# SCH_usb_hub_2025-07-05.net
KiCad netlist of a schematic drawn in EasyEDA
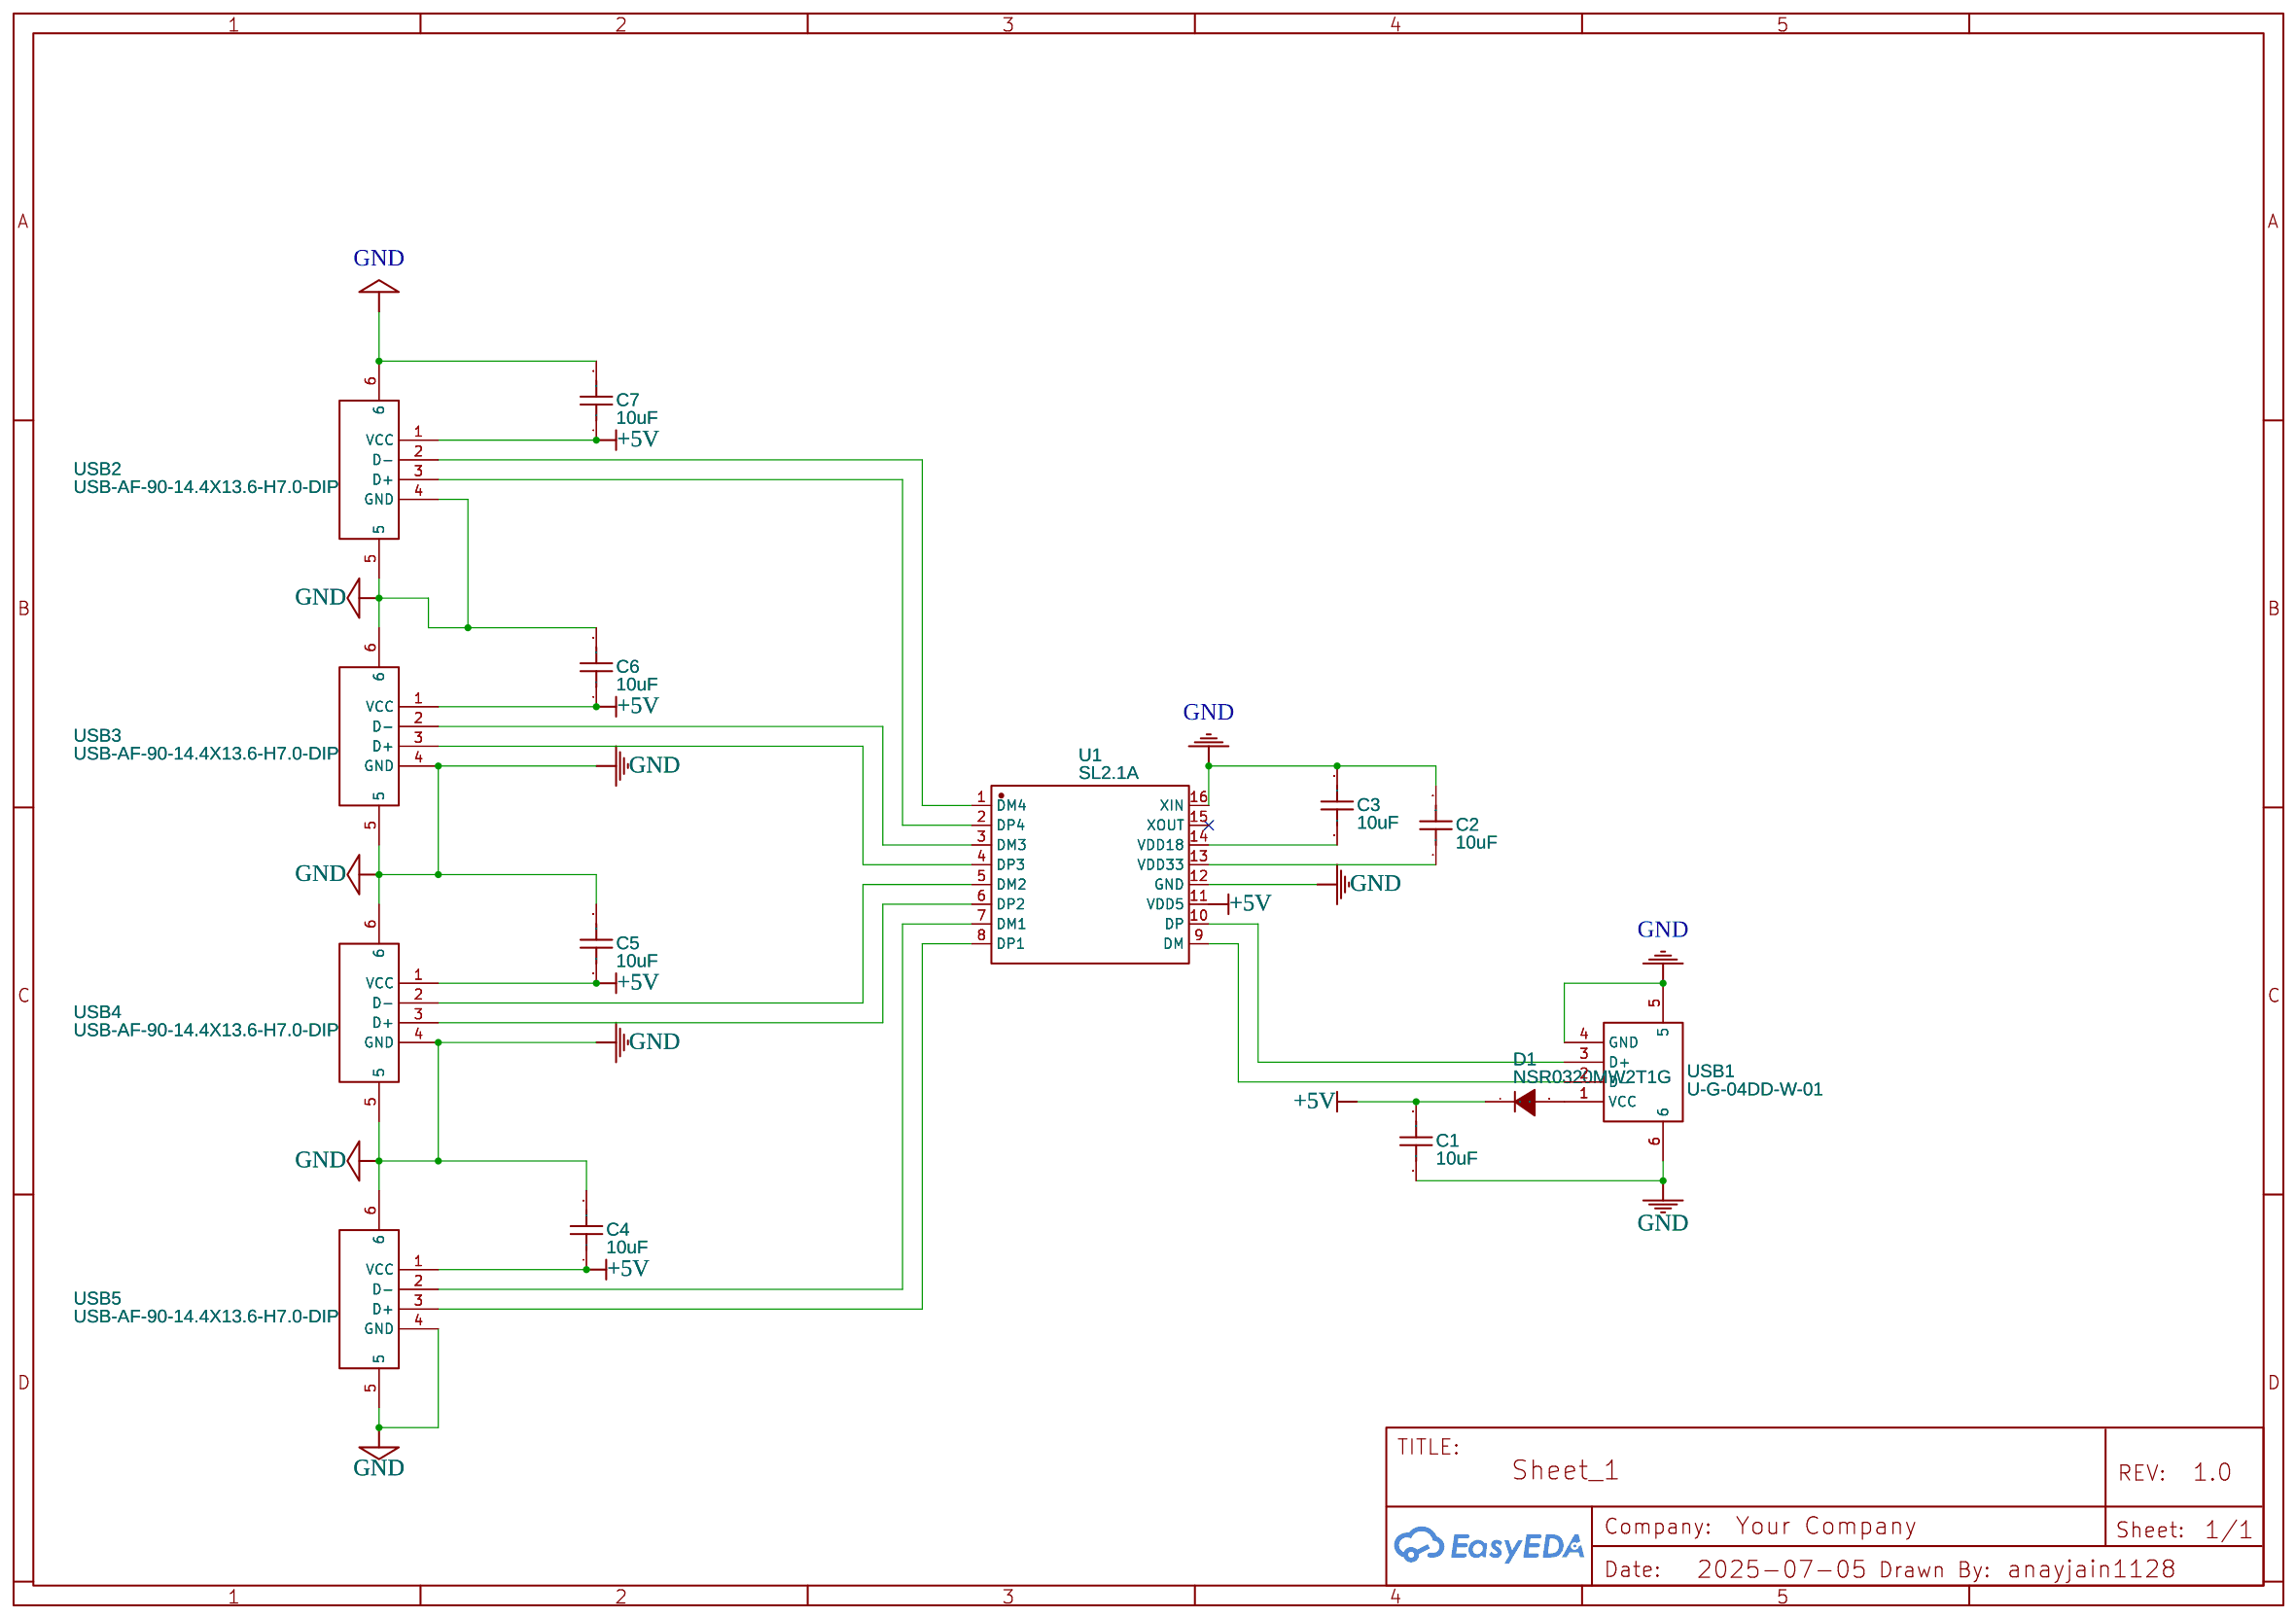
[diagram p0: schematic sheet]

(export (version "E")
  (design (tool "Eeschema 10.0.6"))
  (components
    (comp (ref "C1")
      (value "10uF")
      (fields
        (field (name "Manufacturer Part") "CL10A106KP8NNNC")
        (field (name "Manufacturer") "SAMSUNG(三星)")
      )
      (libsource (lib "") (part "CL10A106KP8NNNC"))
    )
    (comp (ref "C2")
      (value "10uF")
      (fields
        (field (name "Manufacturer Part") "CL10A106KP8NNNC")
        (field (name "Manufacturer") "SAMSUNG(三星)")
      )
      (libsource (lib "") (part "CL10A106KP8NNNC"))
    )
    (comp (ref "C3")
      (value "10uF")
      (fields
        (field (name "Manufacturer Part") "CL10A106KP8NNNC")
        (field (name "Manufacturer") "SAMSUNG(三星)")
      )
      (libsource (lib "") (part "CL10A106KP8NNNC"))
    )
    (comp (ref "C4")
      (value "10uF")
      (fields
        (field (name "Manufacturer Part") "CL10A106KP8NNNC")
        (field (name "Manufacturer") "SAMSUNG(三星)")
      )
      (libsource (lib "") (part "CL10A106KP8NNNC"))
    )
    (comp (ref "C5")
      (value "10uF")
      (fields
        (field (name "Manufacturer Part") "CL10A106KP8NNNC")
        (field (name "Manufacturer") "SAMSUNG(三星)")
      )
      (libsource (lib "") (part "CL10A106KP8NNNC"))
    )
    (comp (ref "C6")
      (value "10uF")
      (fields
        (field (name "Manufacturer Part") "CL10A106KP8NNNC")
        (field (name "Manufacturer") "SAMSUNG(三星)")
      )
      (libsource (lib "") (part "CL10A106KP8NNNC"))
    )
    (comp (ref "C7")
      (value "10uF")
      (fields
        (field (name "Manufacturer Part") "CL10A106KP8NNNC")
        (field (name "Manufacturer") "SAMSUNG(三星)")
      )
      (libsource (lib "") (part "CL10A106KP8NNNC"))
    )
    (comp (ref "D1")
      (value "NSR0320MW2T1G")
      (fields (field (name "Manufacturer") "onsemi(安森美)"))
      (libsource (lib "") (part "NSR0320MW2T1G"))
    )
    (comp (ref "U1")
      (value "SL2.1A")
      (fields (field (name "Manufacturer") "CoreChips(和芯润德)"))
      (libsource (lib "") (part "SL2.1A"))
    )
    (comp (ref "USB1")
      (value "U-G-04DD-W-01")
      (fields (field (name "Manufacturer Part") "U-G-O4DD-W-1") (field (name "Manufacturer") "韩国韩荣"))
      (libsource (lib "") (part "U-G-04DD-W-01"))
    )
    (comp (ref "USB2")
      (value "USB-AF-90-14.4X13.6-H7.0-DIP")
      (fields (field (name "Manufacturer Part") "903-131A1011D10100") (field (name "Manufacturer") "精拓金"))
      (libsource (lib "") (part "USB-AF-90-14.4X13.6-H7.0-DIP"))
    )
    (comp (ref "USB3")
      (value "USB-AF-90-14.4X13.6-H7.0-DIP")
      (fields (field (name "Manufacturer Part") "903-131A1011D10100") (field (name "Manufacturer") "精拓金"))
      (libsource (lib "") (part "USB-AF-90-14.4X13.6-H7.0-DIP"))
    )
    (comp (ref "USB4")
      (value "USB-AF-90-14.4X13.6-H7.0-DIP")
      (fields (field (name "Manufacturer Part") "903-131A1011D10100") (field (name "Manufacturer") "精拓金"))
      (libsource (lib "") (part "USB-AF-90-14.4X13.6-H7.0-DIP"))
    )
    (comp (ref "USB5")
      (value "USB-AF-90-14.4X13.6-H7.0-DIP")
      (fields (field (name "Manufacturer Part") "903-131A1011D10100") (field (name "Manufacturer") "精拓金"))
      (libsource (lib "") (part "USB-AF-90-14.4X13.6-H7.0-DIP"))
    )
  )
  (nets
    (net (code "1") (name "+5V") (class "Default")
      (node (ref "C1") (pin "2") (pinfunction "2_2") (pintype "unspecified"))
      (node (ref "C4") (pin "1") (pinfunction "1_1") (pintype "unspecified"))
      (node (ref "C5") (pin "1") (pinfunction "1_1") (pintype "unspecified"))
      (node (ref "C6") (pin "1") (pinfunction "1_1") (pintype "unspecified"))
      (node (ref "C7") (pin "1") (pinfunction "1_1") (pintype "unspecified"))
      (node (ref "D1") (pin "1") (pinfunction "C_1") (pintype "unspecified"))
      (node (ref "U1") (pin "11") (pinfunction "VDD5_11") (pintype "unspecified"))
      (node (ref "USB2") (pin "1") (pinfunction "VCC_1") (pintype "unspecified"))
      (node (ref "USB3") (pin "1") (pinfunction "VCC_1") (pintype "unspecified"))
      (node (ref "USB4") (pin "1") (pinfunction "VCC_1") (pintype "unspecified"))
      (node (ref "USB5") (pin "1") (pinfunction "VCC_1") (pintype "unspecified"))
    )
    (net (code "2") (name "GND") (class "Default")
      (node (ref "C1") (pin "1") (pinfunction "1_1") (pintype "unspecified"))
      (node (ref "C2") (pin "2") (pinfunction "2_2") (pintype "unspecified"))
      (node (ref "C3") (pin "2") (pinfunction "2_2") (pintype "unspecified"))
      (node (ref "C4") (pin "2") (pinfunction "2_2") (pintype "unspecified"))
      (node (ref "C5") (pin "2") (pinfunction "2_2") (pintype "unspecified"))
      (node (ref "C6") (pin "2") (pinfunction "2_2") (pintype "unspecified"))
      (node (ref "C7") (pin "2") (pinfunction "2_2") (pintype "unspecified"))
      (node (ref "U1") (pin "12") (pinfunction "GND_12") (pintype "unspecified"))
      (node (ref "U1") (pin "16") (pinfunction "XIN_16") (pintype "unspecified"))
      (node (ref "USB1") (pin "4") (pinfunction "GND_4") (pintype "unspecified"))
      (node (ref "USB1") (pin "5") (pinfunction "5_5") (pintype "unspecified"))
      (node (ref "USB1") (pin "6") (pinfunction "6_6") (pintype "unspecified"))
      (node (ref "USB2") (pin "4") (pinfunction "GND_4") (pintype "unspecified"))
      (node (ref "USB2") (pin "5") (pinfunction "5_5") (pintype "unspecified"))
      (node (ref "USB2") (pin "6") (pinfunction "6_6") (pintype "unspecified"))
      (node (ref "USB3") (pin "4") (pinfunction "GND_4") (pintype "unspecified"))
      (node (ref "USB3") (pin "5") (pinfunction "5_5") (pintype "unspecified"))
      (node (ref "USB3") (pin "6") (pinfunction "6_6") (pintype "unspecified"))
      (node (ref "USB4") (pin "4") (pinfunction "GND_4") (pintype "unspecified"))
      (node (ref "USB4") (pin "5") (pinfunction "5_5") (pintype "unspecified"))
      (node (ref "USB4") (pin "6") (pinfunction "6_6") (pintype "unspecified"))
      (node (ref "USB5") (pin "4") (pinfunction "GND_4") (pintype "unspecified"))
      (node (ref "USB5") (pin "5") (pinfunction "5_5") (pintype "unspecified"))
      (node (ref "USB5") (pin "6") (pinfunction "6_6") (pintype "unspecified"))
    )
    (net (code "3") (name "Net-(D1-A)") (class "Default")
      (node (ref "D1") (pin "2") (pinfunction "A_2") (pintype "unspecified"))
      (node (ref "USB1") (pin "1") (pinfunction "VCC_1") (pintype "unspecified"))
    )
    (net (code "4") (name "Net-(U1-DM)") (class "Default")
      (node (ref "U1") (pin "9") (pinfunction "DM_9") (pintype "unspecified"))
      (node (ref "USB1") (pin "2") (pinfunction "D-_2") (pintype "unspecified"))
    )
    (net (code "5") (name "Net-(U1-DM1)") (class "Default")
      (node (ref "U1") (pin "7") (pinfunction "DM1_7") (pintype "unspecified"))
      (node (ref "USB5") (pin "2") (pinfunction "D-_2") (pintype "unspecified"))
    )
    (net (code "6") (name "Net-(U1-DM2)") (class "Default")
      (node (ref "U1") (pin "5") (pinfunction "DM2_5") (pintype "unspecified"))
      (node (ref "USB4") (pin "2") (pinfunction "D-_2") (pintype "unspecified"))
    )
    (net (code "7") (name "Net-(U1-DM3)") (class "Default")
      (node (ref "U1") (pin "3") (pinfunction "DM3_3") (pintype "unspecified"))
      (node (ref "USB3") (pin "2") (pinfunction "D-_2") (pintype "unspecified"))
    )
    (net (code "8") (name "Net-(U1-DM4)") (class "Default")
      (node (ref "U1") (pin "1") (pinfunction "DM4_1") (pintype "unspecified"))
      (node (ref "USB2") (pin "2") (pinfunction "D-_2") (pintype "unspecified"))
    )
    (net (code "9") (name "Net-(U1-DP)") (class "Default")
      (node (ref "U1") (pin "10") (pinfunction "DP_10") (pintype "unspecified"))
      (node (ref "USB1") (pin "3") (pinfunction "D+_3") (pintype "unspecified"))
    )
    (net (code "10") (name "Net-(U1-DP1)") (class "Default")
      (node (ref "U1") (pin "8") (pinfunction "DP1_8") (pintype "unspecified"))
      (node (ref "USB5") (pin "3") (pinfunction "D+_3") (pintype "unspecified"))
    )
    (net (code "11") (name "Net-(U1-DP2)") (class "Default")
      (node (ref "U1") (pin "6") (pinfunction "DP2_6") (pintype "unspecified"))
      (node (ref "USB4") (pin "3") (pinfunction "D+_3") (pintype "unspecified"))
    )
    (net (code "12") (name "Net-(U1-DP3)") (class "Default")
      (node (ref "U1") (pin "4") (pinfunction "DP3_4") (pintype "unspecified"))
      (node (ref "USB3") (pin "3") (pinfunction "D+_3") (pintype "unspecified"))
    )
    (net (code "13") (name "Net-(U1-DP4)") (class "Default")
      (node (ref "U1") (pin "2") (pinfunction "DP4_2") (pintype "unspecified"))
      (node (ref "USB2") (pin "3") (pinfunction "D+_3") (pintype "unspecified"))
    )
    (net (code "14") (name "Net-(U1-VDD18)") (class "Default")
      (node (ref "C3") (pin "1") (pinfunction "1_1") (pintype "unspecified"))
      (node (ref "U1") (pin "14") (pinfunction "VDD18_14") (pintype "unspecified"))
    )
    (net (code "15") (name "Net-(U1-VDD33)") (class "Default")
      (node (ref "C2") (pin "1") (pinfunction "1_1") (pintype "unspecified"))
      (node (ref "U1") (pin "13") (pinfunction "VDD33_13") (pintype "unspecified"))
    )
    (net (code "16") (name "unconnected-(U1-XOUT-Pad15)") (class "Default")
      (node (ref "U1") (pin "15") (pinfunction "XOUT_15") (pintype "unspecified+no_connect"))
    )
  )
)
